# v2164_quad_VCA_0402_DIL.net
KiCad netlist of a schematic drawn in EAGLE
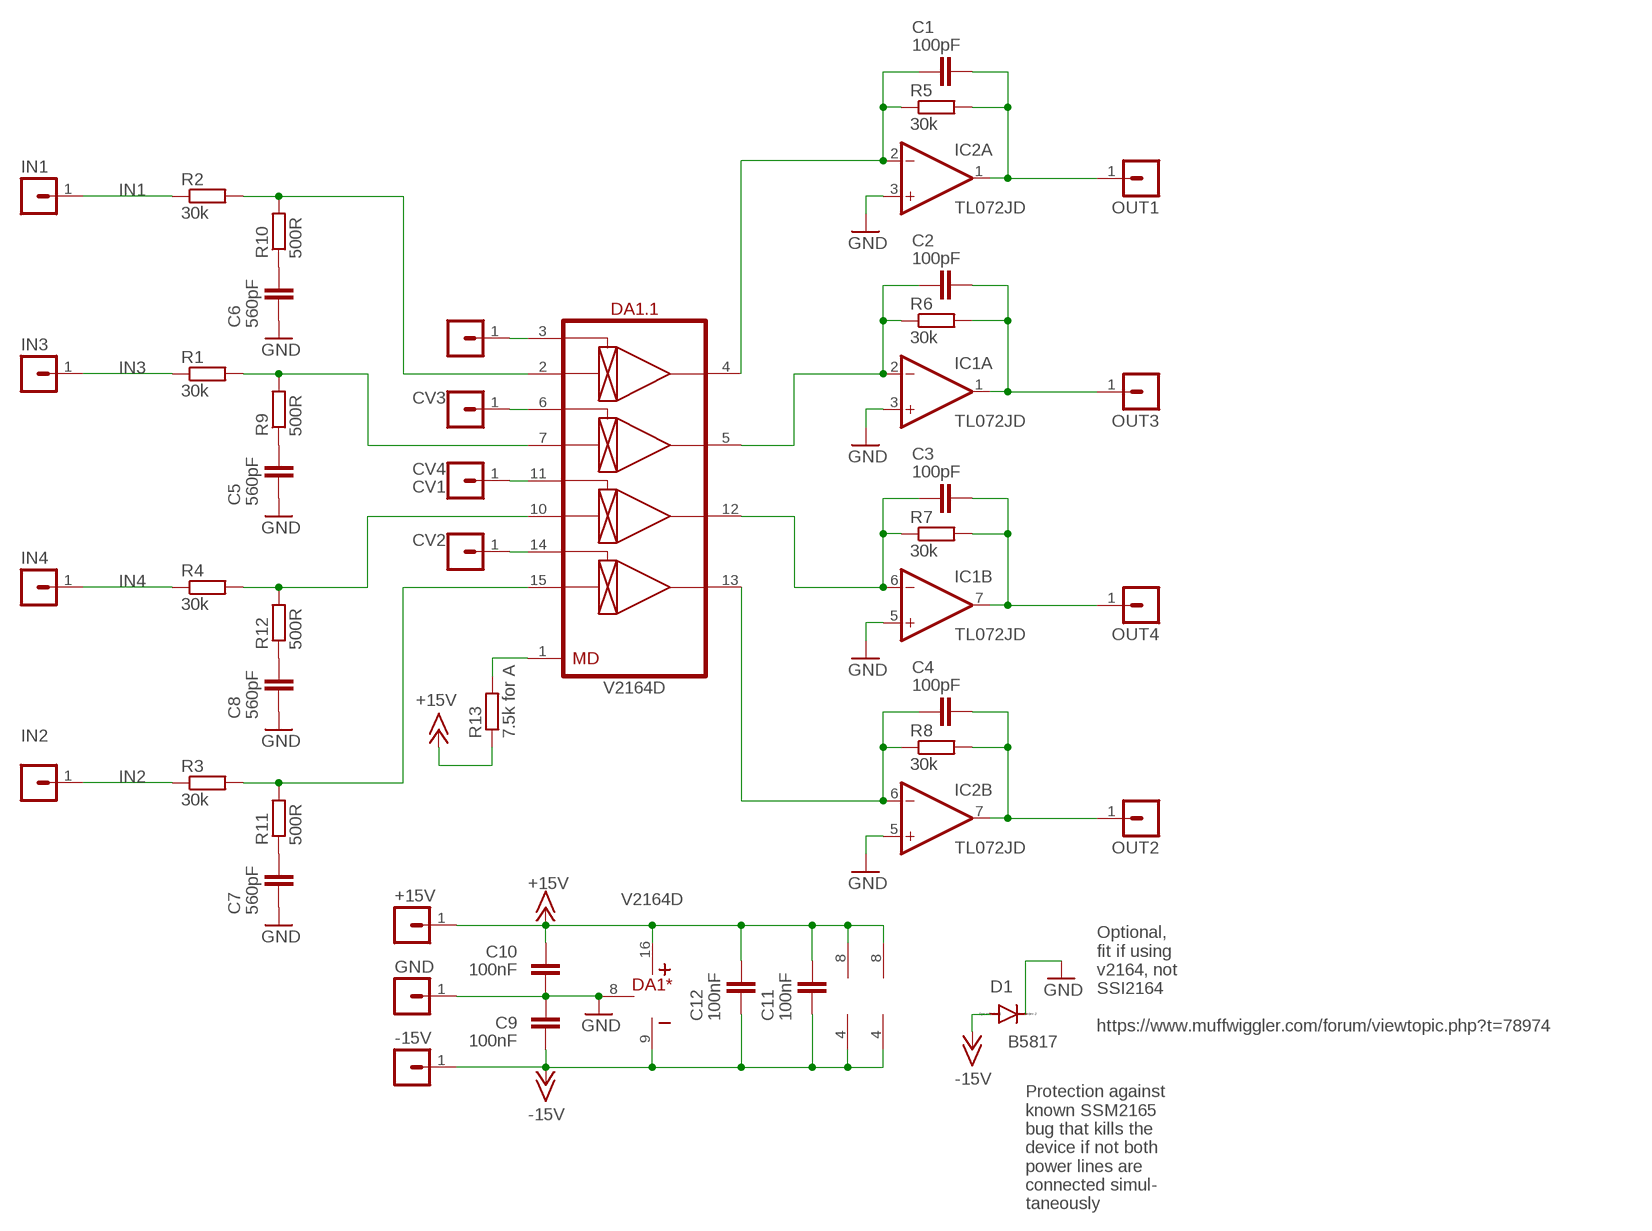
[diagram p0: schematic, sheet 1]

(export (version "E")
  (design (tool "Eeschema 10.0.6"))
  (components
    (comp (ref "+15V")
      (value "MA01-1JP")
      (footprint "eagle-import:SIP-PIN01-1J")
      (libsource (lib "eagle-import") (part "MA01-1JP"))
    )
    (comp (ref "-15V")
      (value "MA01-1JP")
      (footprint "eagle-import:SIP-PIN01-1J")
      (libsource (lib "eagle-import") (part "MA01-1JP"))
    )
    (comp (ref "C1")
      (value "100pF")
      (footprint "eagle-import:C0402")
      (libsource (lib "eagle-import") (part "C-EUC0402"))
    )
    (comp (ref "C2")
      (value "100pF")
      (footprint "eagle-import:C0402")
      (libsource (lib "eagle-import") (part "C-EUC0402"))
    )
    (comp (ref "C3")
      (value "100pF")
      (footprint "eagle-import:C0402")
      (libsource (lib "eagle-import") (part "C-EUC0402"))
    )
    (comp (ref "C4")
      (value "100pF")
      (footprint "eagle-import:C0402")
      (libsource (lib "eagle-import") (part "C-EUC0402"))
    )
    (comp (ref "C5")
      (value "560pF")
      (footprint "eagle-import:C0603")
      (libsource (lib "eagle-import") (part "C-EUC0603"))
    )
    (comp (ref "C6")
      (value "560pF")
      (footprint "eagle-import:C0603")
      (libsource (lib "eagle-import") (part "C-EUC0603"))
    )
    (comp (ref "C7")
      (value "560pF")
      (footprint "eagle-import:C0603")
      (libsource (lib "eagle-import") (part "C-EUC0603"))
    )
    (comp (ref "C8")
      (value "560pF")
      (footprint "eagle-import:C0603")
      (libsource (lib "eagle-import") (part "C-EUC0603"))
    )
    (comp (ref "C9")
      (value "100nF")
      (footprint "eagle-import:C0402")
      (libsource (lib "eagle-import") (part "C-EUC0402"))
    )
    (comp (ref "C10")
      (value "100nF")
      (footprint "eagle-import:C0402")
      (libsource (lib "eagle-import") (part "C-EUC0402"))
    )
    (comp (ref "C11")
      (value "100nF")
      (footprint "eagle-import:C0402")
      (libsource (lib "eagle-import") (part "C-EUC0402"))
    )
    (comp (ref "C12")
      (value "100nF")
      (footprint "eagle-import:C0402")
      (libsource (lib "eagle-import") (part "C-EUC0402"))
    )
    (comp (ref "CV1")
      (value "MA01-1JP")
      (footprint "eagle-import:SIP-PIN01-1J")
      (libsource (lib "eagle-import") (part "MA01-1JP"))
    )
    (comp (ref "CV2")
      (value "MA01-1JP")
      (footprint "eagle-import:SIP-PIN01-1J")
      (libsource (lib "eagle-import") (part "MA01-1JP"))
    )
    (comp (ref "CV3")
      (value "MA01-1JP")
      (footprint "eagle-import:SIP-PIN01-1J")
      (libsource (lib "eagle-import") (part "MA01-1JP"))
    )
    (comp (ref "CV4")
      (value "MA01-1JP")
      (footprint "eagle-import:SIP-PIN01-1J")
      (libsource (lib "eagle-import") (part "MA01-1JP"))
    )
    (comp (ref "D1")
      (value "B5817")
      (footprint "eagle-import:SOD323-R")
      (libsource (lib "eagle-import") (part "DIODE-SOD323-R"))
    )
    (comp (ref "DA1")
      (value "V2164D")
      (footprint "eagle-import:DIP-16")
      (libsource (lib "eagle-import") (part "V2164D"))
    )
    (comp (ref "GND")
      (value "MA01-1JP")
      (footprint "eagle-import:SIP-PIN01-1J")
      (libsource (lib "eagle-import") (part "MA01-1JP"))
    )
    (comp (ref "IC1")
      (value "TL072JD")
      (footprint "eagle-import:SO08J")
      (libsource (lib "eagle-import") (part "TL072JD"))
    )
    (comp (ref "IC2")
      (value "TL072JD")
      (footprint "eagle-import:SO08J")
      (libsource (lib "eagle-import") (part "TL072JD"))
    )
    (comp (ref "IN1")
      (value "MA01-1JP")
      (footprint "eagle-import:SIP-PIN01-1J")
      (libsource (lib "eagle-import") (part "MA01-1JP"))
    )
    (comp (ref "IN2")
      (value "MA01-1JP")
      (footprint "eagle-import:SIP-PIN01-1J")
      (libsource (lib "eagle-import") (part "MA01-1JP"))
    )
    (comp (ref "IN3")
      (value "MA01-1JP")
      (footprint "eagle-import:SIP-PIN01-1J")
      (libsource (lib "eagle-import") (part "MA01-1JP"))
    )
    (comp (ref "IN4")
      (value "MA01-1JP")
      (footprint "eagle-import:SIP-PIN01-1J")
      (libsource (lib "eagle-import") (part "MA01-1JP"))
    )
    (comp (ref "OUT1")
      (value "MA01-1JP")
      (footprint "eagle-import:SIP-PIN01-1J")
      (libsource (lib "eagle-import") (part "MA01-1JP"))
    )
    (comp (ref "OUT2")
      (value "MA01-1JP")
      (footprint "eagle-import:SIP-PIN01-1J")
      (libsource (lib "eagle-import") (part "MA01-1JP"))
    )
    (comp (ref "OUT3")
      (value "MA01-1JP")
      (footprint "eagle-import:SIP-PIN01-1J")
      (libsource (lib "eagle-import") (part "MA01-1JP"))
    )
    (comp (ref "OUT4")
      (value "MA01-1JP")
      (footprint "eagle-import:SIP-PIN01-1J")
      (libsource (lib "eagle-import") (part "MA01-1JP"))
    )
    (comp (ref "R1")
      (value "30k")
      (footprint "eagle-import:R0402")
      (libsource (lib "eagle-import") (part "R-EU_R0402"))
    )
    (comp (ref "R2")
      (value "30k")
      (footprint "eagle-import:R0402")
      (libsource (lib "eagle-import") (part "R-EU_R0402"))
    )
    (comp (ref "R3")
      (value "30k")
      (footprint "eagle-import:R0402")
      (libsource (lib "eagle-import") (part "R-EU_R0402"))
    )
    (comp (ref "R4")
      (value "30k")
      (footprint "eagle-import:R0402")
      (libsource (lib "eagle-import") (part "R-EU_R0402"))
    )
    (comp (ref "R5")
      (value "30k")
      (footprint "eagle-import:R0402")
      (libsource (lib "eagle-import") (part "R-EU_R0402"))
    )
    (comp (ref "R6")
      (value "30k")
      (footprint "eagle-import:R0402")
      (libsource (lib "eagle-import") (part "R-EU_R0402"))
    )
    (comp (ref "R7")
      (value "30k")
      (footprint "eagle-import:R0402")
      (libsource (lib "eagle-import") (part "R-EU_R0402"))
    )
    (comp (ref "R8")
      (value "30k")
      (footprint "eagle-import:R0402")
      (libsource (lib "eagle-import") (part "R-EU_R0402"))
    )
    (comp (ref "R9")
      (value "500R")
      (footprint "eagle-import:R0402")
      (libsource (lib "eagle-import") (part "R-EU_R0402"))
    )
    (comp (ref "R10")
      (value "500R")
      (footprint "eagle-import:R0402")
      (libsource (lib "eagle-import") (part "R-EU_R0402"))
    )
    (comp (ref "R11")
      (value "500R")
      (footprint "eagle-import:R0402")
      (libsource (lib "eagle-import") (part "R-EU_R0402"))
    )
    (comp (ref "R12")
      (value "500R")
      (footprint "eagle-import:R0402")
      (libsource (lib "eagle-import") (part "R-EU_R0402"))
    )
    (comp (ref "R13")
      (value "7.5k for A")
      (footprint "eagle-import:R0402")
      (libsource (lib "eagle-import") (part "R-EU_R0402"))
    )
  )
  (nets
    (net (code "1") (name "+15V") (class "Default")
      (node (ref "+15V") (pin "1") (pinfunction "1_1") (pintype "passive"))
      (node (ref "C10") (pin "2") (pinfunction "2_2") (pintype "passive"))
      (node (ref "C11") (pin "2") (pinfunction "2_2") (pintype "passive"))
      (node (ref "C12") (pin "2") (pinfunction "2_2") (pintype "passive"))
      (node (ref "DA1") (pin "16") (pinfunction "V+_16") (pintype "power_in"))
      (node (ref "IC1") (pin "8") (pinfunction "V+_8") (pintype "power_in"))
      (node (ref "IC2") (pin "8") (pinfunction "V+_8") (pintype "power_in"))
      (node (ref "R13") (pin "1") (pinfunction "1_1") (pintype "passive"))
    )
    (net (code "2") (name "-15V") (class "Default")
      (node (ref "-15V") (pin "1") (pinfunction "1_1") (pintype "passive"))
      (node (ref "C11") (pin "1") (pinfunction "1_1") (pintype "passive"))
      (node (ref "C12") (pin "1") (pinfunction "1_1") (pintype "passive"))
      (node (ref "C9") (pin "1") (pinfunction "1_1") (pintype "passive"))
      (node (ref "D1") (pin "A") (pinfunction "A_A") (pintype "passive"))
      (node (ref "DA1") (pin "9") (pinfunction "V-_9") (pintype "power_in"))
      (node (ref "IC1") (pin "4") (pinfunction "V-_4") (pintype "power_in"))
      (node (ref "IC2") (pin "4") (pinfunction "V-_4") (pintype "power_in"))
    )
    (net (code "3") (name "/IN1") (class "Default")
      (node (ref "IN1") (pin "1") (pinfunction "1_1") (pintype "passive"))
      (node (ref "R2") (pin "1") (pinfunction "1_1") (pintype "passive"))
    )
    (net (code "4") (name "/IN2") (class "Default")
      (node (ref "IN2") (pin "1") (pinfunction "1_1") (pintype "passive"))
      (node (ref "R3") (pin "1") (pinfunction "1_1") (pintype "passive"))
    )
    (net (code "5") (name "/IN3") (class "Default")
      (node (ref "IN3") (pin "1") (pinfunction "1_1") (pintype "passive"))
      (node (ref "R1") (pin "1") (pinfunction "1_1") (pintype "passive"))
    )
    (net (code "6") (name "/IN4") (class "Default")
      (node (ref "IN4") (pin "1") (pinfunction "1_1") (pintype "passive"))
      (node (ref "R4") (pin "1") (pinfunction "1_1") (pintype "passive"))
    )
    (net (code "7") (name "GND") (class "Default")
      (node (ref "C10") (pin "1") (pinfunction "1_1") (pintype "passive"))
      (node (ref "C5") (pin "1") (pinfunction "1_1") (pintype "passive"))
      (node (ref "C6") (pin "1") (pinfunction "1_1") (pintype "passive"))
      (node (ref "C7") (pin "1") (pinfunction "1_1") (pintype "passive"))
      (node (ref "C8") (pin "1") (pinfunction "1_1") (pintype "passive"))
      (node (ref "C9") (pin "2") (pinfunction "2_2") (pintype "passive"))
      (node (ref "D1") (pin "C") (pinfunction "C_C") (pintype "passive"))
      (node (ref "DA1") (pin "8") (pinfunction "GND_8") (pintype "power_in"))
      (node (ref "GND") (pin "1") (pinfunction "1_1") (pintype "passive"))
      (node (ref "IC1") (pin "3") (pinfunction "+IN_3") (pintype "input"))
      (node (ref "IC1") (pin "5") (pinfunction "+IN_5") (pintype "input"))
      (node (ref "IC2") (pin "3") (pinfunction "+IN_3") (pintype "input"))
      (node (ref "IC2") (pin "5") (pinfunction "+IN_5") (pintype "input"))
    )
    (net (code "8") (name "Net-(C5-Pad2)") (class "Default")
      (node (ref "C5") (pin "2") (pinfunction "2_2") (pintype "passive"))
      (node (ref "R9") (pin "1") (pinfunction "1_1") (pintype "passive"))
    )
    (net (code "9") (name "Net-(C6-Pad2)") (class "Default")
      (node (ref "C6") (pin "2") (pinfunction "2_2") (pintype "passive"))
      (node (ref "R10") (pin "1") (pinfunction "1_1") (pintype "passive"))
    )
    (net (code "10") (name "Net-(C7-Pad2)") (class "Default")
      (node (ref "C7") (pin "2") (pinfunction "2_2") (pintype "passive"))
      (node (ref "R11") (pin "1") (pinfunction "1_1") (pintype "passive"))
    )
    (net (code "11") (name "Net-(C8-Pad2)") (class "Default")
      (node (ref "C8") (pin "2") (pinfunction "2_2") (pintype "passive"))
      (node (ref "R12") (pin "1") (pinfunction "1_1") (pintype "passive"))
    )
    (net (code "12") (name "Net-(DA1B-CV1)") (class "Default")
      (node (ref "CV1") (pin "1") (pinfunction "1_1") (pintype "passive"))
      (node (ref "DA1") (pin "3") (pinfunction "CV1_3") (pintype "input"))
    )
    (net (code "13") (name "Net-(DA1B-CV2)") (class "Default")
      (node (ref "CV3") (pin "1") (pinfunction "1_1") (pintype "passive"))
      (node (ref "DA1") (pin "6") (pinfunction "CV2_6") (pintype "input"))
    )
    (net (code "14") (name "Net-(DA1B-CV3)") (class "Default")
      (node (ref "CV4") (pin "1") (pinfunction "1_1") (pintype "passive"))
      (node (ref "DA1") (pin "11") (pinfunction "CV3_11") (pintype "input"))
    )
    (net (code "15") (name "Net-(DA1B-CV4)") (class "Default")
      (node (ref "CV2") (pin "1") (pinfunction "1_1") (pintype "passive"))
      (node (ref "DA1") (pin "14") (pinfunction "CV4_14") (pintype "input"))
    )
    (net (code "16") (name "Net-(DA1B-IN1)") (class "Default")
      (node (ref "DA1") (pin "2") (pinfunction "IN1_2") (pintype "input"))
      (node (ref "R10") (pin "2") (pinfunction "2_2") (pintype "passive"))
      (node (ref "R2") (pin "2") (pinfunction "2_2") (pintype "passive"))
    )
    (net (code "17") (name "Net-(DA1B-IN2)") (class "Default")
      (node (ref "DA1") (pin "7") (pinfunction "IN2_7") (pintype "input"))
      (node (ref "R1") (pin "2") (pinfunction "2_2") (pintype "passive"))
      (node (ref "R9") (pin "2") (pinfunction "2_2") (pintype "passive"))
    )
    (net (code "18") (name "Net-(DA1B-IN3)") (class "Default")
      (node (ref "DA1") (pin "10") (pinfunction "IN3_10") (pintype "input"))
      (node (ref "R12") (pin "2") (pinfunction "2_2") (pintype "passive"))
      (node (ref "R4") (pin "2") (pinfunction "2_2") (pintype "passive"))
    )
    (net (code "19") (name "Net-(DA1B-IN4)") (class "Default")
      (node (ref "DA1") (pin "15") (pinfunction "IN4_15") (pintype "input"))
      (node (ref "R11") (pin "2") (pinfunction "2_2") (pintype "passive"))
      (node (ref "R3") (pin "2") (pinfunction "2_2") (pintype "passive"))
    )
    (net (code "20") (name "Net-(DA1B-MD)") (class "Default")
      (node (ref "DA1") (pin "1") (pinfunction "MD_1") (pintype "output"))
      (node (ref "R13") (pin "2") (pinfunction "2_2") (pintype "passive"))
    )
    (net (code "21") (name "Net-(DA1B-OUT1)") (class "Default")
      (node (ref "C1") (pin "1") (pinfunction "1_1") (pintype "passive"))
      (node (ref "DA1") (pin "4") (pinfunction "OUT1_4") (pintype "output"))
      (node (ref "IC2") (pin "2") (pinfunction "-IN_2") (pintype "input"))
      (node (ref "R5") (pin "1") (pinfunction "1_1") (pintype "passive"))
    )
    (net (code "22") (name "Net-(DA1B-OUT2)") (class "Default")
      (node (ref "C2") (pin "1") (pinfunction "1_1") (pintype "passive"))
      (node (ref "DA1") (pin "5") (pinfunction "OUT2_5") (pintype "output"))
      (node (ref "IC1") (pin "2") (pinfunction "-IN_2") (pintype "input"))
      (node (ref "R6") (pin "1") (pinfunction "1_1") (pintype "passive"))
    )
    (net (code "23") (name "Net-(DA1B-OUT3)") (class "Default")
      (node (ref "C3") (pin "1") (pinfunction "1_1") (pintype "passive"))
      (node (ref "DA1") (pin "12") (pinfunction "OUT3_12") (pintype "output"))
      (node (ref "IC1") (pin "6") (pinfunction "-IN_6") (pintype "input"))
      (node (ref "R7") (pin "1") (pinfunction "1_1") (pintype "passive"))
    )
    (net (code "24") (name "Net-(DA1B-OUT4)") (class "Default")
      (node (ref "C4") (pin "1") (pinfunction "1_1") (pintype "passive"))
      (node (ref "DA1") (pin "13") (pinfunction "OUT4_13") (pintype "output"))
      (node (ref "IC2") (pin "6") (pinfunction "-IN_6") (pintype "input"))
      (node (ref "R8") (pin "1") (pinfunction "1_1") (pintype "passive"))
    )
    (net (code "25") (name "Net-(IC1A-OUT)") (class "Default")
      (node (ref "C2") (pin "2") (pinfunction "2_2") (pintype "passive"))
      (node (ref "IC1") (pin "1") (pinfunction "OUT_1") (pintype "output"))
      (node (ref "OUT3") (pin "1") (pinfunction "1_1") (pintype "passive"))
      (node (ref "R6") (pin "2") (pinfunction "2_2") (pintype "passive"))
    )
    (net (code "26") (name "Net-(IC1B-OUT)") (class "Default")
      (node (ref "C3") (pin "2") (pinfunction "2_2") (pintype "passive"))
      (node (ref "IC1") (pin "7") (pinfunction "OUT_7") (pintype "output"))
      (node (ref "OUT4") (pin "1") (pinfunction "1_1") (pintype "passive"))
      (node (ref "R7") (pin "2") (pinfunction "2_2") (pintype "passive"))
    )
    (net (code "27") (name "Net-(IC2A-OUT)") (class "Default")
      (node (ref "C1") (pin "2") (pinfunction "2_2") (pintype "passive"))
      (node (ref "IC2") (pin "1") (pinfunction "OUT_1") (pintype "output"))
      (node (ref "OUT1") (pin "1") (pinfunction "1_1") (pintype "passive"))
      (node (ref "R5") (pin "2") (pinfunction "2_2") (pintype "passive"))
    )
    (net (code "28") (name "Net-(IC2B-OUT)") (class "Default")
      (node (ref "C4") (pin "2") (pinfunction "2_2") (pintype "passive"))
      (node (ref "IC2") (pin "7") (pinfunction "OUT_7") (pintype "output"))
      (node (ref "OUT2") (pin "1") (pinfunction "1_1") (pintype "passive"))
      (node (ref "R8") (pin "2") (pinfunction "2_2") (pintype "passive"))
    )
  )
)
